# CON_ETHERNET.net
KiCad netlist of a schematic drawn in Altium Designer
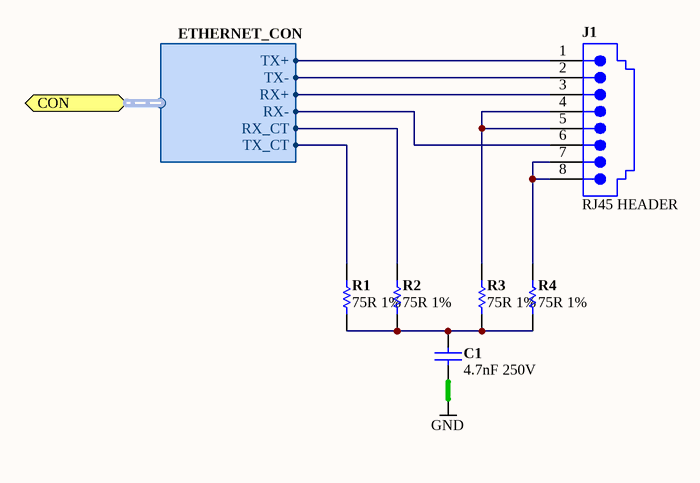
[diagram p0: CON_ETHERNET.SchDoc]

(export (version "E")
  (design (tool "Eeschema 10.0.6"))
  (components
    (comp (ref "C1")
      (value "4.7nF 250V")
      (footprint "CAPM7163")
      (description "Capacitor, Ceramic, 4.7nF 20% 250V Panasonic BC J Lead (CAPM7163) Y5V")
      (fields (field (name "TOLERANCE") "20% %"))
      (libsource (lib "AltiumDesignLibrary") (part "CAP-NP"))
    )
    (comp (ref "J1")
      (value "RJ45 HEADER")
      (footprint "15-43-6233")
      (description "Connector, RJ45 Socket, Right-Angle, 8 Way (Ethernet), PCM8P8C")
      (libsource (lib "AltiumDesignLibrary") (part "CON-RJ45-8-RA"))
    )
    (comp (ref "R1")
      (value "75R 1%")
      (footprint "RESC1005-STAR")
      (description "Resistor, 75R 1% 0402")
      (fields (field (name "TOLERANCE") "1 %"))
      (libsource (lib "AltiumDesignLibrary") (part "RES"))
    )
    (comp (ref "R2")
      (value "75R 1%")
      (footprint "RESC1005-STAR")
      (description "Resistor, 75R 1% 0402")
      (fields (field (name "TOLERANCE") "1 %"))
      (libsource (lib "AltiumDesignLibrary") (part "RES"))
    )
    (comp (ref "R3")
      (value "75R 1%")
      (footprint "RESC1005-STAR")
      (description "Resistor, 75R 1% 0402")
      (fields (field (name "TOLERANCE") "1 %"))
      (libsource (lib "AltiumDesignLibrary") (part "RES"))
    )
    (comp (ref "R4")
      (value "75R 1%")
      (footprint "RESC1005-STAR")
      (description "Resistor, 75R 1% 0402")
      (fields (field (name "TOLERANCE") "1 %"))
      (libsource (lib "AltiumDesignLibrary") (part "RES"))
    )
  )
  (nets
    (net (code "2") (name "/RX+") (class "Default")
      (node (ref "J1") (pin "3") (pinfunction "3_3") (pintype "passive"))
    )
    (net (code "3") (name "/RX-") (class "Default")
      (node (ref "J1") (pin "6") (pinfunction "6_6") (pintype "passive"))
    )
    (net (code "4") (name "/RX_CT") (class "Default")
      (node (ref "R2") (pin "2") (pinfunction "2_2") (pintype "passive"))
    )
    (net (code "5") (name "/TX+") (class "Default")
      (node (ref "J1") (pin "1") (pinfunction "1_1") (pintype "passive"))
    )
    (net (code "6") (name "/TX-") (class "Default")
      (node (ref "J1") (pin "2") (pinfunction "2_2") (pintype "passive"))
    )
    (net (code "7") (name "/TX_CT") (class "Default")
      (node (ref "R1") (pin "2") (pinfunction "2_2") (pintype "passive"))
    )
    (net (code "9") (name "GND") (class "Default")
      (node (ref "C1") (pin "1") (pinfunction "1_1") (pintype "passive"))
    )
    (net (code "10") (name "Net-(C1-Pad2)") (class "Default")
      (node (ref "C1") (pin "2") (pinfunction "2_2") (pintype "passive"))
      (node (ref "R1") (pin "1") (pinfunction "1_1") (pintype "passive"))
      (node (ref "R2") (pin "1") (pinfunction "1_1") (pintype "passive"))
      (node (ref "R3") (pin "1") (pinfunction "1_1") (pintype "passive"))
      (node (ref "R4") (pin "1") (pinfunction "1_1") (pintype "passive"))
    )
    (net (code "11") (name "Net-(J1-Pad4)") (class "Default")
      (node (ref "J1") (pin "4") (pinfunction "4_4") (pintype "passive"))
      (node (ref "J1") (pin "5") (pinfunction "5_5") (pintype "passive"))
      (node (ref "R3") (pin "2") (pinfunction "2_2") (pintype "passive"))
    )
    (net (code "12") (name "Net-(J1-Pad7)") (class "Default")
      (node (ref "J1") (pin "7") (pinfunction "7_7") (pintype "passive"))
      (node (ref "J1") (pin "8") (pinfunction "8_8") (pintype "passive"))
      (node (ref "R4") (pin "2") (pinfunction "2_2") (pintype "passive"))
    )
  )
)
